# esp32final.net
KiCad netlist of a schematic drawn in Altium Designer
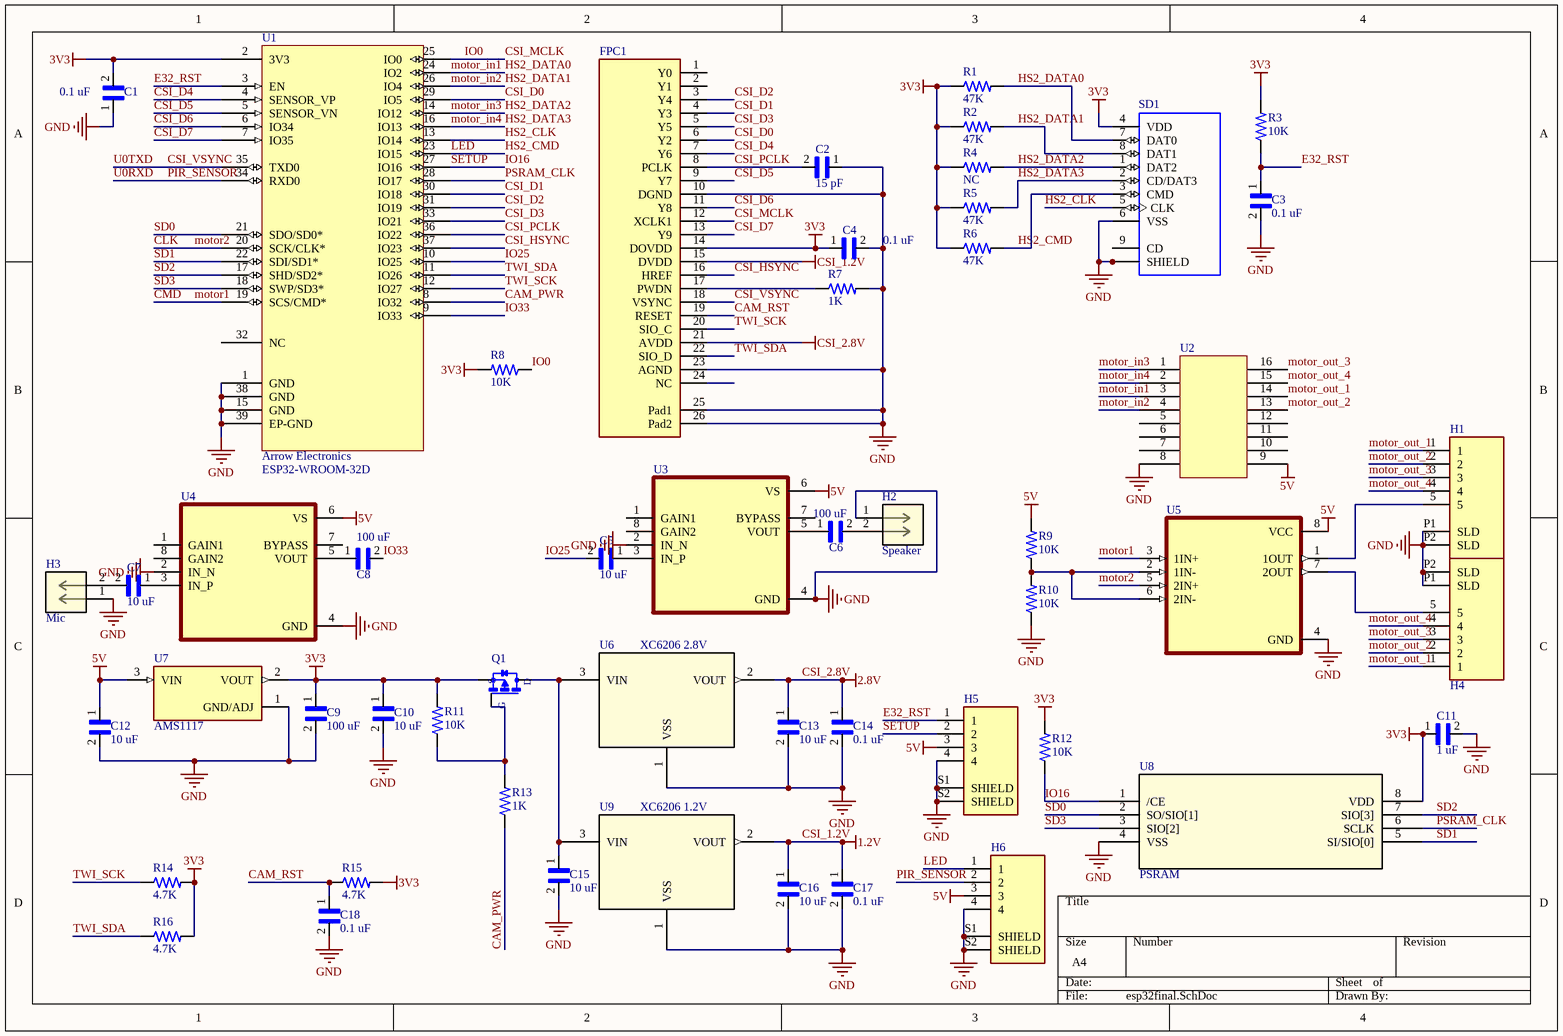
[diagram p0: esp32final.SchDoc]

(export (version "E")
  (design (tool "Eeschema 10.0.6"))
  (components
    (comp (ref "C1")
      (value "0.1 uF")
      (footprint "CAP 0402")
      (description "GCM155R71E333JA55D")
      (libsource (lib "") (part "CAP 0402_2"))
    )
    (comp (ref "C2")
      (value "15 pF")
      (footprint "CAP 0603")
      (description "LD033C471KAB2A")
      (libsource (lib "linkkien") (part "CAP 0603"))
    )
    (comp (ref "C3")
      (value "0.1 uF")
      (footprint "CAP 0402")
      (description "GCM155R71E333JA55D")
      (libsource (lib "") (part "CAP 0402_1"))
    )
    (comp (ref "C4")
      (value "0.1 uF")
      (footprint "CAP 0402")
      (description "GCM155R71E333JA55D")
      (libsource (lib "linkkien") (part "CAP 0402"))
    )
    (comp (ref "C5")
      (value "10 uF")
      (footprint "CAP 0603")
      (description "LD033C471KAB2A")
      (libsource (lib "linkkien") (part "CAP 0603"))
    )
    (comp (ref "C6")
      (value "100 uF")
      (footprint "Tantalum CAP")
      (description "SMD-2")
      (libsource (lib "linkkien") (part "Tantalum CAP"))
    )
    (comp (ref "C7")
      (value "10 uF")
      (footprint "CAP 0603")
      (description "LD033C471KAB2A")
      (libsource (lib "linkkien") (part "CAP 0603"))
    )
    (comp (ref "C8")
      (value "100 uF")
      (footprint "Tantalum CAP")
      (description "SMD-2")
      (libsource (lib "linkkien") (part "Tantalum CAP"))
    )
    (comp (ref "C9") (value "100 uF") (footprint "Tantalum CAP") (libsource (lib "") (part "Tantalum CAP_1")))
    (comp (ref "C10")
      (value "10 uF")
      (footprint "CAP 0603")
      (description "LD033C471KAB2A")
      (libsource (lib "") (part "CAP 0603_1"))
    )
    (comp (ref "C11")
      (value "1 uF")
      (footprint "CAP 0402")
      (description "GCM155R71E333JA55D")
      (libsource (lib "linkkien") (part "CAP 0402"))
    )
    (comp (ref "C12")
      (value "10 uF")
      (footprint "CAP 0603")
      (description "LD033C471KAB2A")
      (libsource (lib "") (part "CAP 0603_1"))
    )
    (comp (ref "C13")
      (value "10 uF")
      (footprint "CAP 0603")
      (description "LD033C471KAB2A")
      (libsource (lib "") (part "CAP 0603_1"))
    )
    (comp (ref "C14")
      (value "0.1 uF")
      (footprint "CAP 0402")
      (description "GCM155R71E333JA55D")
      (libsource (lib "") (part "CAP 0402_1"))
    )
    (comp (ref "C15")
      (value "10 uF")
      (footprint "CAP 0603")
      (description "LD033C471KAB2A")
      (libsource (lib "") (part "CAP 0603_1"))
    )
    (comp (ref "C16")
      (value "10 uF")
      (footprint "CAP 0603")
      (description "LD033C471KAB2A")
      (libsource (lib "") (part "CAP 0603_1"))
    )
    (comp (ref "C17")
      (value "0.1 uF")
      (footprint "CAP 0402")
      (description "GCM155R71E333JA55D")
      (libsource (lib "") (part "CAP 0402_1"))
    )
    (comp (ref "C18")
      (value "0.1 uF")
      (footprint "CAP 0402")
      (description "GCM155R71E333JA55D")
      (libsource (lib "") (part "CAP 0402_1"))
    )
    (comp (ref "FPC1")
      (value "FPC Connector 26 Pins")
      (footprint "FPC Connector 26 Pins")
      (libsource (lib "linkkien") (part "FPC Connector 26 Pins"))
    )
    (comp (ref "H1")
      (value "Header 5P 1mm")
      (footprint "Header 5P 1mm")
      (description "BM05B-SRSS-TB(LF)(SN)")
      (libsource (lib "") (part "Header 5P 1mm_1"))
    )
    (comp (ref "H2")
      (value "Speaker")
      (footprint "Header 2P 1MM")
      (description "BM02B-SRSS-TB (LF)(SN)")
      (libsource (lib "linkkien") (part "Header 2P 1mm"))
    )
    (comp (ref "H3")
      (value "Mic")
      (footprint "Header 2P 1MM")
      (description "BM02B-SRSS-TB (LF)(SN)")
      (libsource (lib "") (part "Header 2P 1mm_1"))
    )
    (comp (ref "H4")
      (value "Header 5P 1mm")
      (footprint "Header 5P 1mm")
      (description "BM05B-SRSS-TB(LF)(SN)")
      (libsource (lib "linkkien") (part "Header 5P 1mm"))
    )
    (comp (ref "H5")
      (value "Header 4P 1mm")
      (footprint "Header 4P 1mm")
      (description "BM04B-SRSS-TB(LF)(SN)")
      (libsource (lib "linkkien") (part "Header 4P 1mm"))
    )
    (comp (ref "H6")
      (value "Header 4P 1mm")
      (footprint "Header 4P 1mm")
      (description "BM04B-SRSS-TB(LF)(SN)")
      (libsource (lib "linkkien") (part "Header 4P 1mm"))
    )
    (comp (ref "Q1")
      (value "P-MOS SOT-23-3")
      (footprint "P-MOS SOT-23-3")
      (description "FDN352AP")
      (libsource (lib "linkkien") (part "P-MOS SOT-23-3"))
    )
    (comp (ref "R1") (value "47K") (footprint "RES 0402") (libsource (lib "linkkien") (part "RES 0402")))
    (comp (ref "R2") (value "47K") (footprint "RES 0402") (libsource (lib "linkkien") (part "RES 0402")))
    (comp (ref "R3") (value "10K") (footprint "RES 0402") (libsource (lib "linkkien") (part "RES 0402")))
    (comp (ref "R4") (value "NC") (footprint "RES 0402") (libsource (lib "linkkien") (part "RES 0402")))
    (comp (ref "R5") (value "47K") (footprint "RES 0402") (libsource (lib "linkkien") (part "RES 0402")))
    (comp (ref "R6") (value "47K") (footprint "RES 0402") (libsource (lib "linkkien") (part "RES 0402")))
    (comp (ref "R7") (value "1K") (footprint "RES 0402") (libsource (lib "linkkien") (part "RES 0402")))
    (comp (ref "R8") (value "10K") (footprint "RES 0402") (libsource (lib "linkkien") (part "RES 0402")))
    (comp (ref "R9") (value "10K") (footprint "RES 0402") (libsource (lib "linkkien") (part "RES 0402")))
    (comp (ref "R10") (value "10K") (footprint "RES 0402") (libsource (lib "linkkien") (part "RES 0402")))
    (comp (ref "R11") (value "10K") (footprint "RES 0402") (libsource (lib "linkkien") (part "RES 0402")))
    (comp (ref "R12") (value "10K") (footprint "RES 0402") (libsource (lib "linkkien") (part "RES 0402")))
    (comp (ref "R13") (value "1K") (footprint "RES 0402") (libsource (lib "linkkien") (part "RES 0402")))
    (comp (ref "R14") (value "4.7K") (footprint "RES 0402") (libsource (lib "linkkien") (part "RES 0402")))
    (comp (ref "R15") (value "4.7K") (footprint "RES 0402") (libsource (lib "linkkien") (part "RES 0402")))
    (comp (ref "R16") (value "4.7K") (footprint "RES 0402") (libsource (lib "linkkien") (part "RES 0402")))
    (comp (ref "SD1")
      (value "Micro SD TF")
      (footprint "Micro SD TF")
      (description "MEM2051-00-195-00-A")
      (libsource (lib "linkkien") (part "Micro SD TF"))
    )
    (comp (ref "U1")
      (value "ESP32-WROOM-32D")
      (footprint "ESP32-WROOM-32D")
      (fields
        (field (name "SUPPLIER 1") "Arrow Electronics")
        (field (name "SUPPLIER PART NUMBER 1") "ESP32-WROOM-32D")
      )
      (libsource (lib "esp32shematic") (part "ESP32-WROOM-32D"))
    )
    (comp (ref "U2")
      (value "ULN 2003A")
      (footprint "ULN 2003A")
      (libsource (lib "linkkien") (part "ULN 2003A"))
    )
    (comp (ref "U3")
      (value "LM386")
      (footprint "PCBC_LM386")
      (description "LM386M-1/NOPB. Wide Input Voltage Low Power Audio Amplifier with Internal Gain 8-SOIC 0 to 70")
      (libsource (lib "lm386") (part "LM386"))
    )
    (comp (ref "U4")
      (value "LM386")
      (footprint "PCBC_LM386")
      (description "LM386M-1/NOPB. Wide Input Voltage Low Power Audio Amplifier with Internal Gain 8-SOIC 0 to 70")
      (libsource (lib "lm386") (part "LM386"))
    )
    (comp (ref "U5")
      (value "LM 393 SOIC-8")
      (footprint "LM 393 SOIC-8")
      (description "LM393DR")
      (libsource (lib "linkkien") (part "LM 393 SOIC-8"))
    )
    (comp (ref "U6")
      (value "XC6206 2.8V")
      (footprint "XC6206 2.8V")
      (description "XC6206P282MR-G")
      (libsource (lib "linkkien") (part "XC6206 2.8V"))
    )
    (comp (ref "U7") (value "AMS1117") (footprint "AMS1117") (libsource (lib "linkkien") (part "AMS1117")))
    (comp (ref "U8") (value "PSRAM") (footprint "PSRAM") (libsource (lib "linkkien") (part "PSRAM")))
    (comp (ref "U9")
      (value "XC6206 1.2V")
      (footprint "XC6206 1.2V")
      (description "XC6206P122MR-G")
      (libsource (lib "linkkien") (part "XC6206 1.2V"))
    )
  )
  (nets
    (net (code "1") (name "/CAM_PWR") (class "Default")
      (node (ref "R13") (pin "1") (pinfunction "1_1") (pintype "passive"))
      (node (ref "U1") (pin "8") (pinfunction "IO32_8") (pintype "bidirectional"))
    )
    (net (code "2") (name "/CAM_RST") (class "Default")
      (node (ref "C18") (pin "1") (pinfunction "1_1") (pintype "passive"))
      (node (ref "FPC1") (pin "19") (pinfunction "RESET_19") (pintype "passive"))
      (node (ref "R15") (pin "1") (pinfunction "1_1") (pintype "passive"))
    )
    (net (code "3") (name "/CLK") (class "Default")
      (node (ref "U1") (pin "20") (pinfunction "SCK/CLK*_20") (pintype "bidirectional"))
      (node (ref "U5") (pin "5") (pinfunction "2IN+_5") (pintype "input"))
    )
    (net (code "4") (name "/CMD") (class "Default")
      (node (ref "U1") (pin "19") (pinfunction "SCS/CMD*_19") (pintype "bidirectional"))
      (node (ref "U5") (pin "3") (pinfunction "1IN+_3") (pintype "input"))
    )
    (net (code "5") (name "/CSI_D0") (class "Default")
      (node (ref "FPC1") (pin "6") (pinfunction "Y2_6") (pintype "passive"))
      (node (ref "U1") (pin "29") (pinfunction "IO5_29") (pintype "bidirectional"))
    )
    (net (code "6") (name "/CSI_D1") (class "Default")
      (node (ref "FPC1") (pin "4") (pinfunction "Y3_4") (pintype "passive"))
      (node (ref "U1") (pin "30") (pinfunction "IO18_30") (pintype "bidirectional"))
    )
    (net (code "7") (name "/CSI_D2") (class "Default")
      (node (ref "FPC1") (pin "3") (pinfunction "Y4_3") (pintype "passive"))
      (node (ref "U1") (pin "31") (pinfunction "IO19_31") (pintype "bidirectional"))
    )
    (net (code "8") (name "/CSI_D3") (class "Default")
      (node (ref "FPC1") (pin "5") (pinfunction "Y5_5") (pintype "passive"))
      (node (ref "U1") (pin "33") (pinfunction "IO21_33") (pintype "bidirectional"))
    )
    (net (code "9") (name "/CSI_D4") (class "Default")
      (node (ref "FPC1") (pin "7") (pinfunction "Y6_7") (pintype "passive"))
      (node (ref "U1") (pin "4") (pinfunction "SENSOR_VP_4") (pintype "input"))
    )
    (net (code "10") (name "/CSI_D5") (class "Default")
      (node (ref "FPC1") (pin "9") (pinfunction "Y7_9") (pintype "passive"))
      (node (ref "U1") (pin "5") (pinfunction "SENSOR_VN_5") (pintype "input"))
    )
    (net (code "11") (name "/CSI_D6") (class "Default")
      (node (ref "FPC1") (pin "11") (pinfunction "Y8_11") (pintype "passive"))
      (node (ref "U1") (pin "6") (pinfunction "IO34_6") (pintype "input"))
    )
    (net (code "12") (name "/CSI_D7") (class "Default")
      (node (ref "FPC1") (pin "13") (pinfunction "Y9_13") (pintype "passive"))
      (node (ref "U1") (pin "7") (pinfunction "IO35_7") (pintype "input"))
    )
    (net (code "13") (name "/CSI_HSYNC") (class "Default")
      (node (ref "FPC1") (pin "16") (pinfunction "HREF_16") (pintype "passive"))
      (node (ref "U1") (pin "37") (pinfunction "IO23_37") (pintype "bidirectional"))
    )
    (net (code "14") (name "/CSI_MCLK") (class "Default")
      (node (ref "FPC1") (pin "12") (pinfunction "XCLK1_12") (pintype "passive"))
      (node (ref "R8") (pin "1") (pinfunction "1_1") (pintype "passive"))
      (node (ref "U1") (pin "25") (pinfunction "IO0_25") (pintype "bidirectional"))
    )
    (net (code "15") (name "/CSI_PCLK") (class "Default")
      (node (ref "C2") (pin "2") (pinfunction "2_2") (pintype "passive"))
      (node (ref "FPC1") (pin "8") (pinfunction "PCLK_8") (pintype "passive"))
      (node (ref "U1") (pin "36") (pinfunction "IO22_36") (pintype "bidirectional"))
    )
    (net (code "16") (name "/CSI_VSYNC") (class "Default")
      (node (ref "FPC1") (pin "18") (pinfunction "VSYNC_18") (pintype "passive"))
      (node (ref "U1") (pin "35") (pinfunction "TXD0_35") (pintype "bidirectional"))
    )
    (net (code "17") (name "/E32_RST") (class "Default")
      (node (ref "C3") (pin "1") (pinfunction "1_1") (pintype "passive"))
      (node (ref "H5") (pin "1") (pinfunction "1_1") (pintype "passive"))
      (node (ref "R3") (pin "1") (pinfunction "1_1") (pintype "passive"))
      (node (ref "U1") (pin "3") (pinfunction "EN_3") (pintype "input"))
    )
    (net (code "18") (name "/HS2_CLK") (class "Default")
      (node (ref "SD1") (pin "5") (pinfunction "CLK_5") (pintype "bidirectional"))
      (node (ref "U1") (pin "13") (pinfunction "IO14_13") (pintype "bidirectional"))
    )
    (net (code "19") (name "/HS2_CMD") (class "Default")
      (node (ref "H6") (pin "1") (pinfunction "1_1") (pintype "passive"))
      (node (ref "R6") (pin "2") (pinfunction "2_2") (pintype "passive"))
      (node (ref "SD1") (pin "3") (pinfunction "CMD_3") (pintype "bidirectional"))
      (node (ref "U1") (pin "23") (pinfunction "IO15_23") (pintype "bidirectional"))
    )
    (net (code "20") (name "/HS2_DATA0") (class "Default")
      (node (ref "R1") (pin "2") (pinfunction "2_2") (pintype "passive"))
      (node (ref "SD1") (pin "7") (pinfunction "DAT0_7") (pintype "bidirectional"))
      (node (ref "U1") (pin "24") (pinfunction "IO2_24") (pintype "bidirectional"))
      (node (ref "U2") (pin "3") (pinfunction "IN3_3") (pintype "passive"))
    )
    (net (code "21") (name "/HS2_DATA1") (class "Default")
      (node (ref "R2") (pin "2") (pinfunction "2_2") (pintype "passive"))
      (node (ref "SD1") (pin "8") (pinfunction "DAT1_8") (pintype "bidirectional"))
      (node (ref "U1") (pin "26") (pinfunction "IO4_26") (pintype "bidirectional"))
      (node (ref "U2") (pin "4") (pinfunction "IN4_4") (pintype "passive"))
    )
    (net (code "22") (name "/HS2_DATA2") (class "Default")
      (node (ref "R4") (pin "2") (pinfunction "2_2") (pintype "passive"))
      (node (ref "SD1") (pin "1") (pinfunction "DAT2_1") (pintype "bidirectional"))
      (node (ref "U1") (pin "14") (pinfunction "IO12_14") (pintype "bidirectional"))
      (node (ref "U2") (pin "1") (pinfunction "IN1_1") (pintype "passive"))
    )
    (net (code "23") (name "/HS2_DATA3") (class "Default")
      (node (ref "R5") (pin "2") (pinfunction "2_2") (pintype "passive"))
      (node (ref "SD1") (pin "2") (pinfunction "CD/DAT3_2") (pintype "bidirectional"))
      (node (ref "U1") (pin "16") (pinfunction "IO13_16") (pintype "bidirectional"))
      (node (ref "U2") (pin "2") (pinfunction "IN2_2") (pintype "passive"))
    )
    (net (code "24") (name "/IO16") (class "Default")
      (node (ref "H5") (pin "2") (pinfunction "2_2") (pintype "passive"))
      (node (ref "R12") (pin "1") (pinfunction "1_1") (pintype "passive"))
      (node (ref "U1") (pin "27") (pinfunction "IO16_27") (pintype "bidirectional"))
      (node (ref "U8") (pin "1") (pinfunction "/CE_1") (pintype "passive"))
    )
    (net (code "25") (name "/IO25") (class "Default")
      (node (ref "C5") (pin "2") (pinfunction "2_2") (pintype "passive"))
      (node (ref "U1") (pin "10") (pinfunction "IO25_10") (pintype "bidirectional"))
    )
    (net (code "26") (name "/IO33") (class "Default")
      (node (ref "C8") (pin "2") (pinfunction "2_2") (pintype "passive"))
      (node (ref "U1") (pin "9") (pinfunction "IO33_9") (pintype "bidirectional"))
    )
    (net (code "27") (name "/PIR_SENSOR") (class "Default")
      (node (ref "H6") (pin "2") (pinfunction "2_2") (pintype "passive"))
      (node (ref "U1") (pin "34") (pinfunction "RXD0_34") (pintype "bidirectional"))
    )
    (net (code "28") (name "/PSRAM_CLK") (class "Default")
      (node (ref "U1") (pin "28") (pinfunction "IO17_28") (pintype "bidirectional"))
      (node (ref "U8") (pin "6") (pinfunction "SCLK_6") (pintype "passive"))
    )
    (net (code "29") (name "/SD0") (class "Default")
      (node (ref "U1") (pin "21") (pinfunction "SDO/SD0*_21") (pintype "bidirectional"))
      (node (ref "U8") (pin "2") (pinfunction "SO/SIO[1]_2") (pintype "passive"))
    )
    (net (code "30") (name "/SD1") (class "Default")
      (node (ref "U1") (pin "22") (pinfunction "SDI/SD1*_22") (pintype "bidirectional"))
      (node (ref "U8") (pin "5") (pinfunction "SI/SIO[0]_5") (pintype "passive"))
    )
    (net (code "31") (name "/SD2") (class "Default")
      (node (ref "U1") (pin "17") (pinfunction "SHD/SD2*_17") (pintype "bidirectional"))
      (node (ref "U8") (pin "7") (pinfunction "SIO[3]_7") (pintype "passive"))
    )
    (net (code "32") (name "/SD3") (class "Default")
      (node (ref "U1") (pin "18") (pinfunction "SWP/SD3*_18") (pintype "bidirectional"))
      (node (ref "U8") (pin "3") (pinfunction "SIO[2]_3") (pintype "passive"))
    )
    (net (code "33") (name "/TWI_SCK") (class "Default")
      (node (ref "FPC1") (pin "20") (pinfunction "SIO_C_20") (pintype "passive"))
      (node (ref "R14") (pin "1") (pinfunction "1_1") (pintype "passive"))
      (node (ref "U1") (pin "12") (pinfunction "IO27_12") (pintype "bidirectional"))
    )
    (net (code "34") (name "/TWI_SDA") (class "Default")
      (node (ref "FPC1") (pin "22") (pinfunction "SIO_D_22") (pintype "passive"))
      (node (ref "R16") (pin "1") (pinfunction "1_1") (pintype "passive"))
      (node (ref "U1") (pin "11") (pinfunction "IO26_11") (pintype "bidirectional"))
    )
    (net (code "35") (name "/motor_out_1") (class "Default")
      (node (ref "H1") (pin "1") (pinfunction "1_1") (pintype "passive"))
      (node (ref "H4") (pin "1") (pinfunction "1_1") (pintype "passive"))
      (node (ref "U2") (pin "14") (pinfunction "OUT3_14") (pintype "passive"))
    )
    (net (code "36") (name "/motor_out_2") (class "Default")
      (node (ref "H1") (pin "2") (pinfunction "2_2") (pintype "passive"))
      (node (ref "H4") (pin "2") (pinfunction "2_2") (pintype "passive"))
      (node (ref "U2") (pin "13") (pinfunction "OUT4_13") (pintype "passive"))
    )
    (net (code "37") (name "/motor_out_3") (class "Default")
      (node (ref "H1") (pin "3") (pinfunction "3_3") (pintype "passive"))
      (node (ref "H4") (pin "3") (pinfunction "3_3") (pintype "passive"))
      (node (ref "U2") (pin "16") (pinfunction "OUT1_16") (pintype "passive"))
    )
    (net (code "38") (name "/motor_out_4") (class "Default")
      (node (ref "H1") (pin "4") (pinfunction "4_4") (pintype "passive"))
      (node (ref "H4") (pin "4") (pinfunction "4_4") (pintype "passive"))
      (node (ref "U2") (pin "15") (pinfunction "OUT2_15") (pintype "passive"))
    )
    (net (code "39") (name "1.2V") (class "Default")
      (node (ref "C16") (pin "1") (pinfunction "1_1") (pintype "passive"))
      (node (ref "C17") (pin "1") (pinfunction "1_1") (pintype "passive"))
      (node (ref "FPC1") (pin "15") (pinfunction "DVDD_15") (pintype "passive"))
      (node (ref "U9") (pin "2") (pinfunction "VOUT_2") (pintype "output"))
    )
    (net (code "40") (name "2.8V") (class "Default")
      (node (ref "C13") (pin "1") (pinfunction "1_1") (pintype "passive"))
      (node (ref "C14") (pin "1") (pinfunction "1_1") (pintype "passive"))
      (node (ref "FPC1") (pin "21") (pinfunction "AVDD_21") (pintype "passive"))
      (node (ref "U6") (pin "2") (pinfunction "VOUT_2") (pintype "output"))
    )
    (net (code "41") (name "3V3") (class "Default")
      (node (ref "C1") (pin "2") (pinfunction "2_2") (pintype "passive"))
      (node (ref "C10") (pin "1") (pinfunction "1_1") (pintype "passive"))
      (node (ref "C11") (pin "1") (pinfunction "1_1") (pintype "passive"))
      (node (ref "C4") (pin "1") (pinfunction "1_1") (pintype "passive"))
      (node (ref "C9") (pin "1") (pinfunction "1_1") (pintype "passive"))
      (node (ref "FPC1") (pin "14") (pinfunction "DOVDD_14") (pintype "passive"))
      (node (ref "Q1") (pin "2") (pinfunction "S_2") (pintype "passive"))
      (node (ref "R1") (pin "1") (pinfunction "1_1") (pintype "passive"))
      (node (ref "R11") (pin "2") (pinfunction "2_2") (pintype "passive"))
      (node (ref "R12") (pin "2") (pinfunction "2_2") (pintype "passive"))
      (node (ref "R14") (pin "2") (pinfunction "2_2") (pintype "passive"))
      (node (ref "R15") (pin "2") (pinfunction "2_2") (pintype "passive"))
      (node (ref "R16") (pin "2") (pinfunction "2_2") (pintype "passive"))
      (node (ref "R2") (pin "1") (pinfunction "1_1") (pintype "passive"))
      (node (ref "R3") (pin "2") (pinfunction "2_2") (pintype "passive"))
      (node (ref "R4") (pin "1") (pinfunction "1_1") (pintype "passive"))
      (node (ref "R5") (pin "1") (pinfunction "1_1") (pintype "passive"))
      (node (ref "R6") (pin "1") (pinfunction "1_1") (pintype "passive"))
      (node (ref "R8") (pin "2") (pinfunction "2_2") (pintype "passive"))
      (node (ref "SD1") (pin "4") (pinfunction "VDD_4") (pintype "power_in"))
      (node (ref "U1") (pin "2") (pinfunction "3V3_2") (pintype "power_in"))
      (node (ref "U7") (pin "2") (pinfunction "VOUT_2") (pintype "output"))
      (node (ref "U8") (pin "8") (pinfunction "VDD_8") (pintype "passive"))
    )
    (net (code "42") (name "5V") (class "Default")
      (node (ref "C12") (pin "1") (pinfunction "1_1") (pintype "passive"))
      (node (ref "H5") (pin "3") (pinfunction "3_3") (pintype "passive"))
      (node (ref "H6") (pin "3") (pinfunction "3_3") (pintype "passive"))
      (node (ref "R9") (pin "2") (pinfunction "2_2") (pintype "passive"))
      (node (ref "U2") (pin "9") (pinfunction "DIOTS_9") (pintype "power_in"))
      (node (ref "U3") (pin "6") (pinfunction "VS_6") (pintype "power_in"))
      (node (ref "U4") (pin "6") (pinfunction "VS_6") (pintype "power_in"))
      (node (ref "U5") (pin "8") (pinfunction "VCC_8") (pintype "power_in"))
      (node (ref "U7") (pin "3") (pinfunction "VIN_3") (pintype "input"))
    )
    (net (code "43") (name "GND") (class "Default")
      (node (ref "C1") (pin "1") (pinfunction "1_1") (pintype "passive"))
      (node (ref "C10") (pin "2") (pinfunction "2_2") (pintype "passive"))
      (node (ref "C11") (pin "2") (pinfunction "2_2") (pintype "passive"))
      (node (ref "C12") (pin "2") (pinfunction "2_2") (pintype "passive"))
      (node (ref "C13") (pin "2") (pinfunction "2_2") (pintype "passive"))
      (node (ref "C14") (pin "2") (pinfunction "2_2") (pintype "passive"))
      (node (ref "C15") (pin "2") (pinfunction "2_2") (pintype "passive"))
      (node (ref "C16") (pin "2") (pinfunction "2_2") (pintype "passive"))
      (node (ref "C17") (pin "2") (pinfunction "2_2") (pintype "passive"))
      (node (ref "C18") (pin "2") (pinfunction "2_2") (pintype "passive"))
      (node (ref "C2") (pin "1") (pinfunction "1_1") (pintype "passive"))
      (node (ref "C3") (pin "2") (pinfunction "2_2") (pintype "passive"))
      (node (ref "C4") (pin "2") (pinfunction "2_2") (pintype "passive"))
      (node (ref "C9") (pin "2") (pinfunction "2_2") (pintype "passive"))
      (node (ref "FPC1") (pin "10") (pinfunction "DGND_10") (pintype "passive"))
      (node (ref "FPC1") (pin "23") (pinfunction "AGND_23") (pintype "passive"))
      (node (ref "FPC1") (pin "25") (pinfunction "Pad1_25") (pintype "passive"))
      (node (ref "FPC1") (pin "26") (pinfunction "Pad2_26") (pintype "passive"))
      (node (ref "H1") (pin "P1") (pinfunction "SLD_P1") (pintype "passive"))
      (node (ref "H1") (pin "P2") (pinfunction "SLD_P2") (pintype "passive"))
      (node (ref "H2") (pin "1") (pinfunction "1_1") (pintype "passive"))
      (node (ref "H3") (pin "1") (pinfunction "1_1") (pintype "passive"))
      (node (ref "H4") (pin "P1") (pinfunction "SLD_P1") (pintype "passive"))
      (node (ref "H4") (pin "P2") (pinfunction "SLD_P2") (pintype "passive"))
      (node (ref "H5") (pin "4") (pinfunction "4_4") (pintype "passive"))
      (node (ref "H5") (pin "S1") (pinfunction "SHIELD_S1") (pintype "passive"))
      (node (ref "H5") (pin "S2") (pinfunction "SHIELD_S2") (pintype "passive"))
      (node (ref "H6") (pin "4") (pinfunction "4_4") (pintype "passive"))
      (node (ref "H6") (pin "S1") (pinfunction "SHIELD_S1") (pintype "passive"))
      (node (ref "H6") (pin "S2") (pinfunction "SHIELD_S2") (pintype "passive"))
      (node (ref "R10") (pin "1") (pinfunction "1_1") (pintype "passive"))
      (node (ref "R7") (pin "2") (pinfunction "2_2") (pintype "passive"))
      (node (ref "SD1") (pin "10") (pinfunction "SHIELD_10") (pintype "passive"))
      (node (ref "SD1") (pin "11") (pinfunction "SHIELD_11") (pintype "passive"))
      (node (ref "SD1") (pin "12") (pinfunction "SHIELD_12") (pintype "passive"))
      (node (ref "SD1") (pin "13") (pinfunction "SHIELD_13") (pintype "passive"))
      (node (ref "SD1") (pin "6") (pinfunction "VSS_6") (pintype "power_in"))
      (node (ref "U1") (pin "1") (pinfunction "GND_1") (pintype "power_in"))
      (node (ref "U1") (pin "15") (pinfunction "GND_15") (pintype "power_in"))
      (node (ref "U1") (pin "38") (pinfunction "GND_38") (pintype "power_in"))
      (node (ref "U1") (pin "39") (pinfunction "EP-GND_39") (pintype "power_in"))
      (node (ref "U2") (pin "8") (pinfunction "GND_8") (pintype "power_in"))
      (node (ref "U3") (pin "2") (pinfunction "IN_N_2") (pintype "passive"))
      (node (ref "U3") (pin "4") (pinfunction "GND_4") (pintype "power_in"))
      (node (ref "U4") (pin "2") (pinfunction "IN_N_2") (pintype "passive"))
      (node (ref "U4") (pin "4") (pinfunction "GND_4") (pintype "power_in"))
      (node (ref "U5") (pin "4") (pinfunction "GND_4") (pintype "power_in"))
      (node (ref "U6") (pin "1") (pinfunction "VSS_1") (pintype "passive"))
      (node (ref "U7") (pin "1") (pinfunction "GND/ADJ_1") (pintype "power_in"))
      (node (ref "U8") (pin "4") (pinfunction "VSS_4") (pintype "passive"))
      (node (ref "U9") (pin "1") (pinfunction "VSS_1") (pintype "passive"))
    )
    (net (code "44") (name "Net-(C6-Pad2)") (class "Default")
      (node (ref "C6") (pin "2") (pinfunction "2_2") (pintype "passive"))
      (node (ref "H2") (pin "2") (pinfunction "2_2") (pintype "passive"))
    )
    (net (code "45") (name "Net-(C7-Pad2)") (class "Default")
      (node (ref "C7") (pin "2") (pinfunction "2_2") (pintype "passive"))
      (node (ref "H3") (pin "2") (pinfunction "2_2") (pintype "passive"))
    )
    (net (code "46") (name "Net-(FPC1-PWDN)") (class "Default")
      (node (ref "FPC1") (pin "17") (pinfunction "PWDN_17") (pintype "passive"))
      (node (ref "R7") (pin "1") (pinfunction "1_1") (pintype "passive"))
    )
    (net (code "47") (name "Net-(Q1-D)") (class "Default")
      (node (ref "C15") (pin "1") (pinfunction "1_1") (pintype "passive"))
      (node (ref "Q1") (pin "3") (pinfunction "D_3") (pintype "passive"))
      (node (ref "U6") (pin "3") (pinfunction "VIN_3") (pintype "power_in"))
      (node (ref "U9") (pin "3") (pinfunction "VIN_3") (pintype "power_in"))
    )
    (net (code "48") (name "Net-(Q1-G)") (class "Default")
      (node (ref "Q1") (pin "1") (pinfunction "G_1") (pintype "passive"))
      (node (ref "R11") (pin "1") (pinfunction "1_1") (pintype "passive"))
      (node (ref "R13") (pin "2") (pinfunction "2_2") (pintype "passive"))
    )
    (net (code "49") (name "Net-(U3-IN_P)") (class "Default")
      (node (ref "C5") (pin "1") (pinfunction "1_1") (pintype "passive"))
      (node (ref "U3") (pin "3") (pinfunction "IN_P_3") (pintype "passive"))
    )
    (net (code "50") (name "Net-(U3-VOUT)") (class "Default")
      (node (ref "C6") (pin "1") (pinfunction "1_1") (pintype "passive"))
      (node (ref "U3") (pin "5") (pinfunction "VOUT_5") (pintype "passive"))
    )
    (net (code "51") (name "Net-(U4-IN_P)") (class "Default")
      (node (ref "C7") (pin "1") (pinfunction "1_1") (pintype "passive"))
      (node (ref "U4") (pin "3") (pinfunction "IN_P_3") (pintype "passive"))
    )
    (net (code "52") (name "Net-(U4-VOUT)") (class "Default")
      (node (ref "C8") (pin "1") (pinfunction "1_1") (pintype "passive"))
      (node (ref "U4") (pin "5") (pinfunction "VOUT_5") (pintype "passive"))
    )
    (net (code "53") (name "Net-(U5-1IN-)") (class "Default")
      (node (ref "R10") (pin "2") (pinfunction "2_2") (pintype "passive"))
      (node (ref "R9") (pin "1") (pinfunction "1_1") (pintype "passive"))
      (node (ref "U5") (pin "2") (pinfunction "1IN-_2") (pintype "input"))
      (node (ref "U5") (pin "6") (pinfunction "2IN-_6") (pintype "input"))
    )
    (net (code "54") (name "Net-(U5-1OUT)") (class "Default")
      (node (ref "H1") (pin "5") (pinfunction "5_5") (pintype "passive"))
      (node (ref "U5") (pin "1") (pinfunction "1OUT_1") (pintype "output"))
    )
    (net (code "55") (name "Net-(U5-2OUT)") (class "Default")
      (node (ref "H4") (pin "5") (pinfunction "5_5") (pintype "passive"))
      (node (ref "U5") (pin "7") (pinfunction "2OUT_7") (pintype "output"))
    )
    (net (code "56") (name "unconnected-(FPC1-NC-Pad24)") (class "Default")
      (node (ref "FPC1") (pin "24") (pinfunction "NC_24") (pintype "passive"))
    )
    (net (code "57") (name "unconnected-(FPC1-Y0-Pad1)") (class "Default")
      (node (ref "FPC1") (pin "1") (pinfunction "Y0_1") (pintype "passive"))
    )
    (net (code "58") (name "unconnected-(FPC1-Y1-Pad2)") (class "Default")
      (node (ref "FPC1") (pin "2") (pinfunction "Y1_2") (pintype "passive"))
    )
    (net (code "59") (name "unconnected-(SD1-CD-Pad9)") (class "Default")
      (node (ref "SD1") (pin "9") (pinfunction "CD_9") (pintype "passive"))
    )
    (net (code "60") (name "unconnected-(U1-NC-Pad32)") (class "Default")
      (node (ref "U1") (pin "32") (pinfunction "NC_32") (pintype "passive"))
    )
    (net (code "61") (name "unconnected-(U2-IN5-Pad5)") (class "Default")
      (node (ref "U2") (pin "5") (pinfunction "IN5_5") (pintype "passive"))
    )
    (net (code "62") (name "unconnected-(U2-IN6-Pad6)") (class "Default")
      (node (ref "U2") (pin "6") (pinfunction "IN6_6") (pintype "passive"))
    )
    (net (code "63") (name "unconnected-(U2-IN7-Pad7)") (class "Default")
      (node (ref "U2") (pin "7") (pinfunction "IN7_7") (pintype "passive"))
    )
    (net (code "64") (name "unconnected-(U2-OUT5-Pad12)") (class "Default")
      (node (ref "U2") (pin "12") (pinfunction "OUT5_12") (pintype "passive"))
    )
    (net (code "65") (name "unconnected-(U2-OUT6-Pad11)") (class "Default")
      (node (ref "U2") (pin "11") (pinfunction "OUT6_11") (pintype "passive"))
    )
    (net (code "66") (name "unconnected-(U2-OUT7-Pad10)") (class "Default")
      (node (ref "U2") (pin "10") (pinfunction "OUT7_10") (pintype "passive"))
    )
    (net (code "67") (name "unconnected-(U3-BYPASS-Pad7)") (class "Default")
      (node (ref "U3") (pin "7") (pinfunction "BYPASS_7") (pintype "passive"))
    )
    (net (code "68") (name "unconnected-(U3-GAIN1-Pad1)") (class "Default")
      (node (ref "U3") (pin "1") (pinfunction "GAIN1_1") (pintype "passive"))
    )
    (net (code "69") (name "unconnected-(U3-GAIN2-Pad8)") (class "Default")
      (node (ref "U3") (pin "8") (pinfunction "GAIN2_8") (pintype "passive"))
    )
    (net (code "70") (name "unconnected-(U4-BYPASS-Pad7)") (class "Default")
      (node (ref "U4") (pin "7") (pinfunction "BYPASS_7") (pintype "passive"))
    )
    (net (code "71") (name "unconnected-(U4-GAIN1-Pad1)") (class "Default")
      (node (ref "U4") (pin "1") (pinfunction "GAIN1_1") (pintype "passive"))
    )
    (net (code "72") (name "unconnected-(U4-GAIN2-Pad8)") (class "Default")
      (node (ref "U4") (pin "8") (pinfunction "GAIN2_8") (pintype "passive"))
    )
  )
)
